# 19_-DDR4_260_PIN_CON.net
KiCad netlist of a schematic drawn in Altium Designer
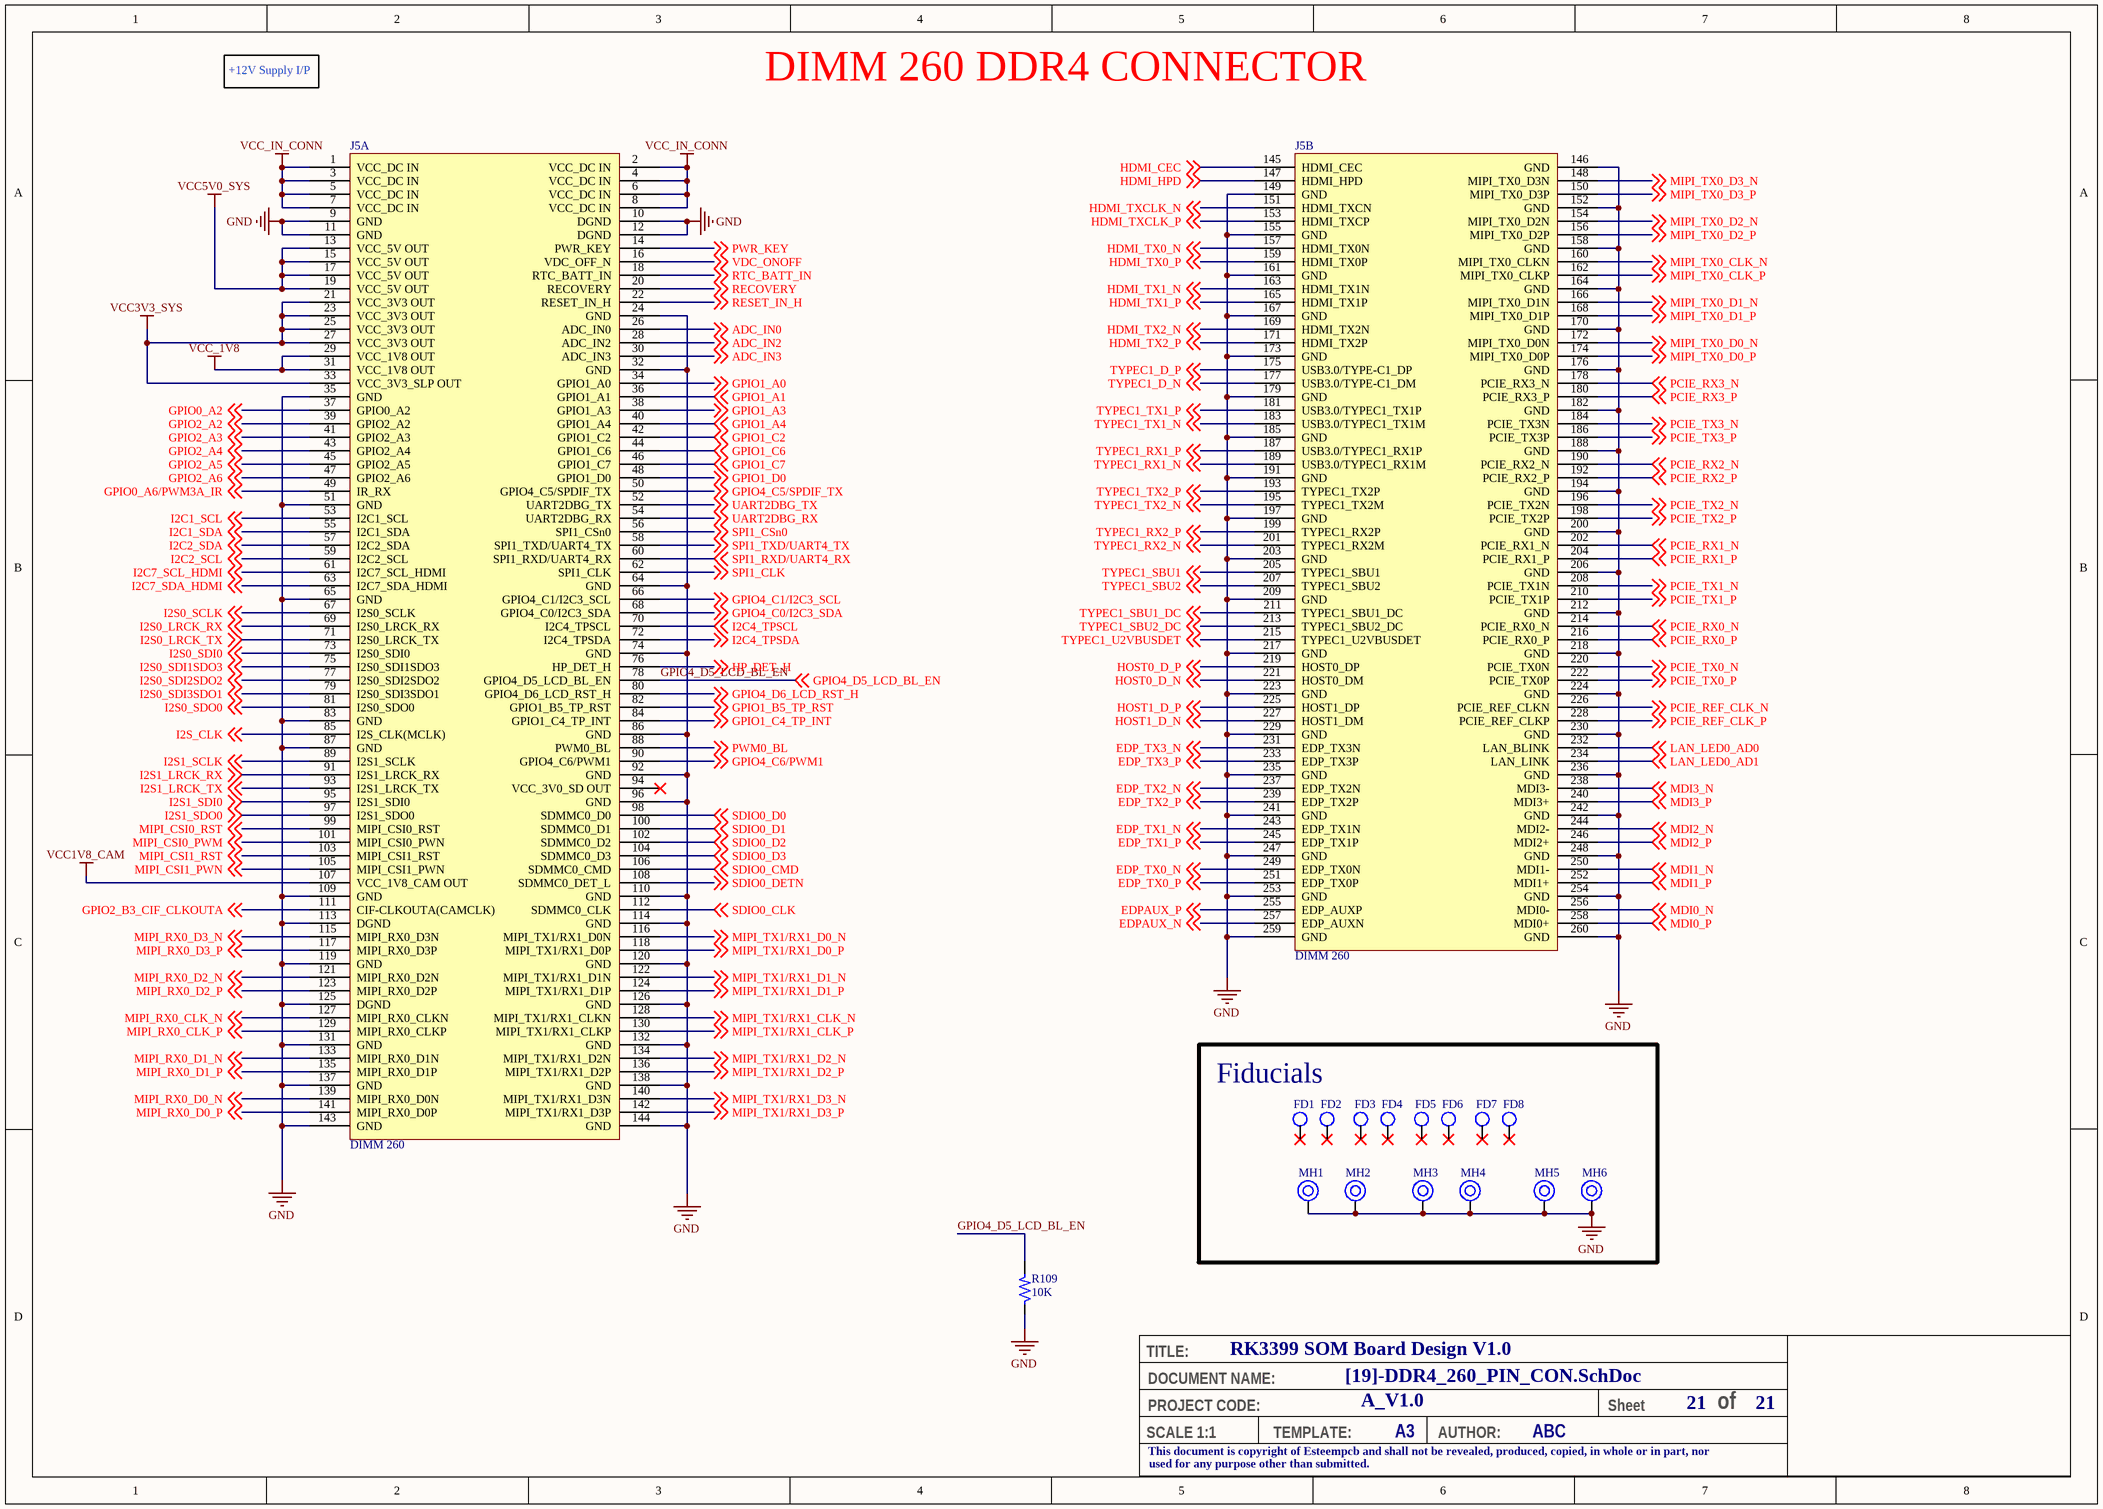
[diagram p0: [19]-DDR4_260_PIN_CON.SchDoc]

(export (version "E")
  (design (tool "Eeschema 10.0.6"))
  (components
    (comp (ref "FD1")
      (value "Fiducial")
      (footprint "FIDUCIAL_50MIL")
      (description "78.7 or 50 mil Fiducials SMD")
      (fields (field (name "MANUFACTURER") "NA"))
      (libsource (lib "EsteemPCB_SOM_Course_intlib") (part "Fiducials"))
    )
    (comp (ref "FD2")
      (value "Fiducial")
      (footprint "FIDUCIAL_50MIL")
      (description "78.7 or 50 mil Fiducials SMD")
      (fields (field (name "MANUFACTURER") "NA"))
      (libsource (lib "EsteemPCB_SOM_Course_intlib") (part "Fiducials"))
    )
    (comp (ref "FD3")
      (value "Fiducial")
      (footprint "FIDUCIAL_50MIL")
      (description "78.7 or 50 mil Fiducials SMD")
      (fields (field (name "MANUFACTURER") "NA"))
      (libsource (lib "EsteemPCB_SOM_Course_intlib") (part "Fiducials"))
    )
    (comp (ref "FD4")
      (value "Fiducial")
      (footprint "FIDUCIAL_50MIL")
      (description "78.7 or 50 mil Fiducials SMD")
      (fields (field (name "MANUFACTURER") "NA"))
      (libsource (lib "EsteemPCB_SOM_Course_intlib") (part "Fiducials"))
    )
    (comp (ref "FD5")
      (value "Fiducial")
      (footprint "FIDUCIAL_50MIL")
      (description "78.7 or 50 mil Fiducials SMD")
      (fields (field (name "MANUFACTURER") "NA"))
      (libsource (lib "EsteemPCB_SOM_Course_intlib") (part "Fiducials"))
    )
    (comp (ref "FD6")
      (value "Fiducial")
      (footprint "FIDUCIAL_50MIL")
      (description "78.7 or 50 mil Fiducials SMD")
      (fields (field (name "MANUFACTURER") "NA"))
      (libsource (lib "EsteemPCB_SOM_Course_intlib") (part "Fiducials"))
    )
    (comp (ref "FD7")
      (value "Fiducial")
      (footprint "FIDUCIAL_50MIL")
      (description "78.7 or 50 mil Fiducials SMD")
      (fields (field (name "MANUFACTURER") "NA"))
      (libsource (lib "EsteemPCB_SOM_Course_intlib") (part "Fiducials"))
    )
    (comp (ref "FD8")
      (value "Fiducial")
      (footprint "FIDUCIAL_50MIL")
      (description "78.7 or 50 mil Fiducials SMD")
      (fields (field (name "MANUFACTURER") "NA"))
      (libsource (lib "EsteemPCB_SOM_Course_intlib") (part "Fiducials"))
    )
    (comp (ref "J5")
      (value "DIMM 260")
      (footprint "DIMM260_DDR4")
      (description "Dimm 260 pin smd plating on pcb")
      (fields (field (name "MANUFACTURER") "NA"))
      (libsource (lib "RK3399 _Module_Schlib") (part "CON-DIMM_260-SMD"))
    )
    (comp (ref "MH1")
      (value "Mounting Hole")
      (footprint "SOM_Mounting")
      (fields (field (name "MANUFACTURER PART NUMBER") "NA"))
      (libsource (lib "EsteemPCB_SOM_Course_intlib") (part "MH_3.5H_6D"))
    )
    (comp (ref "MH2")
      (value "Mounting Hole")
      (footprint "SOM_Mounting")
      (fields (field (name "MANUFACTURER PART NUMBER") "NA"))
      (libsource (lib "EsteemPCB_SOM_Course_intlib") (part "MH_3.5H_6D"))
    )
    (comp (ref "MH3")
      (value "Mounting Hole")
      (footprint "SOM_Mounting")
      (fields (field (name "MANUFACTURER PART NUMBER") "NA"))
      (libsource (lib "EsteemPCB_SOM_Course_intlib") (part "MH_3.5H_6D"))
    )
    (comp (ref "MH4")
      (value "Mounting Hole")
      (footprint "SOM_Mounting")
      (fields (field (name "MANUFACTURER PART NUMBER") "NA"))
      (libsource (lib "EsteemPCB_SOM_Course_intlib") (part "MH_3.5H_6D"))
    )
    (comp (ref "MH5")
      (value "Mounting Hole")
      (footprint "SOM_Mounting")
      (fields (field (name "MANUFACTURER PART NUMBER") "NA"))
      (libsource (lib "EsteemPCB_SOM_Course_intlib") (part "MH_3.5H_6D"))
    )
    (comp (ref "MH6")
      (value "Mounting Hole")
      (footprint "SOM_Mounting")
      (fields (field (name "MANUFACTURER PART NUMBER") "NA"))
      (libsource (lib "EsteemPCB_SOM_Course_intlib") (part "MH_3.5H_6D"))
    )
    (comp (ref "R109")
      (value "10K")
      (footprint "RES_0402")
      (description "10 kOhms ±1% 0.1W, 1/10W Chip Resistor 0402 (1005 Metric) Anti-Sulfur Thin Film")
      (fields
        (field (name "MANUFACTURER") "Vishay Beyschlag/Draloric/BC Components")
        (field (name "MANUFACTURER PART NUMBER") "MCS04020C1002FE000")
      )
      (libsource (lib "RK3399 _Module_Schlib") (part "RES_10K-0.1W-1%-0402"))
    )
  )
  (nets
    (net (code "1") (name "ADC_IN0") (class "Default")
      (node (ref "J5") (pin "26") (pinfunction "ADC_IN0_26") (pintype "passive"))
    )
    (net (code "2") (name "ADC_IN2") (class "Default")
      (node (ref "J5") (pin "28") (pinfunction "ADC_IN2_28") (pintype "passive"))
    )
    (net (code "3") (name "ADC_IN3") (class "Default")
      (node (ref "J5") (pin "30") (pinfunction "ADC_IN3_30") (pintype "passive"))
    )
    (net (code "4") (name "EDPAUX_N") (class "Default")
      (node (ref "J5") (pin "257") (pinfunction "EDP_AUXN_257") (pintype "passive"))
    )
    (net (code "5") (name "EDPAUX_P") (class "Default")
      (node (ref "J5") (pin "255") (pinfunction "EDP_AUXP_255") (pintype "passive"))
    )
    (net (code "6") (name "EDP_TX0_N") (class "Default")
      (node (ref "J5") (pin "249") (pinfunction "EDP_TX0N_249") (pintype "passive"))
    )
    (net (code "7") (name "EDP_TX0_P") (class "Default")
      (node (ref "J5") (pin "251") (pinfunction "EDP_TX0P_251") (pintype "passive"))
    )
    (net (code "8") (name "EDP_TX1_N") (class "Default")
      (node (ref "J5") (pin "243") (pinfunction "EDP_TX1N_243") (pintype "passive"))
    )
    (net (code "9") (name "EDP_TX1_P") (class "Default")
      (node (ref "J5") (pin "245") (pinfunction "EDP_TX1P_245") (pintype "passive"))
    )
    (net (code "10") (name "EDP_TX2_N") (class "Default")
      (node (ref "J5") (pin "237") (pinfunction "EDP_TX2N_237") (pintype "passive"))
    )
    (net (code "11") (name "EDP_TX2_P") (class "Default")
      (node (ref "J5") (pin "239") (pinfunction "EDP_TX2P_239") (pintype "passive"))
    )
    (net (code "12") (name "EDP_TX3_N") (class "Default")
      (node (ref "J5") (pin "231") (pinfunction "EDP_TX3N_231") (pintype "passive"))
    )
    (net (code "13") (name "EDP_TX3_P") (class "Default")
      (node (ref "J5") (pin "233") (pinfunction "EDP_TX3P_233") (pintype "passive"))
    )
    (net (code "14") (name "GND") (class "Default")
      (node (ref "J5") (pin "10") (pinfunction "DGND_10") (pintype "passive"))
      (node (ref "J5") (pin "109") (pinfunction "GND_109") (pintype "passive"))
      (node (ref "J5") (pin "11") (pinfunction "GND_11") (pintype "passive"))
      (node (ref "J5") (pin "110") (pinfunction "GND_110") (pintype "passive"))
      (node (ref "J5") (pin "113") (pinfunction "DGND_113") (pintype "passive"))
      (node (ref "J5") (pin "114") (pinfunction "GND_114") (pintype "passive"))
      (node (ref "J5") (pin "119") (pinfunction "GND_119") (pintype "passive"))
      (node (ref "J5") (pin "12") (pinfunction "DGND_12") (pintype "passive"))
      (node (ref "J5") (pin "120") (pinfunction "GND_120") (pintype "passive"))
      (node (ref "J5") (pin "125") (pinfunction "DGND_125") (pintype "passive"))
      (node (ref "J5") (pin "126") (pinfunction "GND_126") (pintype "passive"))
      (node (ref "J5") (pin "131") (pinfunction "GND_131") (pintype "passive"))
      (node (ref "J5") (pin "132") (pinfunction "GND_132") (pintype "passive"))
      (node (ref "J5") (pin "137") (pinfunction "GND_137") (pintype "passive"))
      (node (ref "J5") (pin "138") (pinfunction "GND_138") (pintype "passive"))
      (node (ref "J5") (pin "143") (pinfunction "GND_143") (pintype "passive"))
      (node (ref "J5") (pin "144") (pinfunction "GND_144") (pintype "passive"))
      (node (ref "J5") (pin "146") (pinfunction "GND_146") (pintype "passive"))
      (node (ref "J5") (pin "149") (pinfunction "GND_149") (pintype "passive"))
      (node (ref "J5") (pin "152") (pinfunction "GND_152") (pintype "passive"))
      (node (ref "J5") (pin "155") (pinfunction "GND_155") (pintype "passive"))
      (node (ref "J5") (pin "158") (pinfunction "GND_158") (pintype "passive"))
      (node (ref "J5") (pin "161") (pinfunction "GND_161") (pintype "passive"))
      (node (ref "J5") (pin "164") (pinfunction "GND_164") (pintype "passive"))
      (node (ref "J5") (pin "167") (pinfunction "GND_167") (pintype "passive"))
      (node (ref "J5") (pin "170") (pinfunction "GND_170") (pintype "passive"))
      (node (ref "J5") (pin "173") (pinfunction "GND_173") (pintype "passive"))
      (node (ref "J5") (pin "176") (pinfunction "GND_176") (pintype "passive"))
      (node (ref "J5") (pin "179") (pinfunction "GND_179") (pintype "passive"))
      (node (ref "J5") (pin "182") (pinfunction "GND_182") (pintype "passive"))
      (node (ref "J5") (pin "185") (pinfunction "GND_185") (pintype "passive"))
      (node (ref "J5") (pin "188") (pinfunction "GND_188") (pintype "passive"))
      (node (ref "J5") (pin "191") (pinfunction "GND_191") (pintype "passive"))
      (node (ref "J5") (pin "194") (pinfunction "GND_194") (pintype "passive"))
      (node (ref "J5") (pin "197") (pinfunction "GND_197") (pintype "passive"))
      (node (ref "J5") (pin "200") (pinfunction "GND_200") (pintype "passive"))
      (node (ref "J5") (pin "203") (pinfunction "GND_203") (pintype "passive"))
      (node (ref "J5") (pin "206") (pinfunction "GND_206") (pintype "passive"))
      (node (ref "J5") (pin "209") (pinfunction "GND_209") (pintype "passive"))
      (node (ref "J5") (pin "212") (pinfunction "GND_212") (pintype "passive"))
      (node (ref "J5") (pin "217") (pinfunction "GND_217") (pintype "passive"))
      (node (ref "J5") (pin "218") (pinfunction "GND_218") (pintype "passive"))
      (node (ref "J5") (pin "223") (pinfunction "GND_223") (pintype "passive"))
      (node (ref "J5") (pin "224") (pinfunction "GND_224") (pintype "passive"))
      (node (ref "J5") (pin "229") (pinfunction "GND_229") (pintype "passive"))
      (node (ref "J5") (pin "230") (pinfunction "GND_230") (pintype "passive"))
      (node (ref "J5") (pin "235") (pinfunction "GND_235") (pintype "passive"))
      (node (ref "J5") (pin "236") (pinfunction "GND_236") (pintype "passive"))
      (node (ref "J5") (pin "24") (pinfunction "GND_24") (pintype "passive"))
      (node (ref "J5") (pin "241") (pinfunction "GND_241") (pintype "passive"))
      (node (ref "J5") (pin "242") (pinfunction "GND_242") (pintype "passive"))
      (node (ref "J5") (pin "247") (pinfunction "GND_247") (pintype "passive"))
      (node (ref "J5") (pin "248") (pinfunction "GND_248") (pintype "passive"))
      (node (ref "J5") (pin "253") (pinfunction "GND_253") (pintype "passive"))
      (node (ref "J5") (pin "254") (pinfunction "GND_254") (pintype "passive"))
      (node (ref "J5") (pin "259") (pinfunction "GND_259") (pintype "passive"))
      (node (ref "J5") (pin "260") (pinfunction "GND_260") (pintype "passive"))
      (node (ref "J5") (pin "32") (pinfunction "GND_32") (pintype "passive"))
      (node (ref "J5") (pin "35") (pinfunction "GND_35") (pintype "passive"))
      (node (ref "J5") (pin "51") (pinfunction "GND_51") (pintype "passive"))
      (node (ref "J5") (pin "64") (pinfunction "GND_64") (pintype "passive"))
      (node (ref "J5") (pin "65") (pinfunction "GND_65") (pintype "passive"))
      (node (ref "J5") (pin "74") (pinfunction "GND_74") (pintype "passive"))
      (node (ref "J5") (pin "83") (pinfunction "GND_83") (pintype "passive"))
      (node (ref "J5") (pin "86") (pinfunction "GND_86") (pintype "passive"))
      (node (ref "J5") (pin "87") (pinfunction "GND_87") (pintype "passive"))
      (node (ref "J5") (pin "9") (pinfunction "GND_9") (pintype "passive"))
      (node (ref "J5") (pin "92") (pinfunction "GND_92") (pintype "passive"))
      (node (ref "J5") (pin "96") (pinfunction "GND_96") (pintype "passive"))
      (node (ref "MH1") (pin "1") (pinfunction "1_1") (pintype "passive"))
      (node (ref "MH2") (pin "1") (pinfunction "1_1") (pintype "passive"))
      (node (ref "MH3") (pin "1") (pinfunction "1_1") (pintype "passive"))
      (node (ref "MH4") (pin "1") (pinfunction "1_1") (pintype "passive"))
      (node (ref "MH5") (pin "1") (pinfunction "1_1") (pintype "passive"))
      (node (ref "MH6") (pin "1") (pinfunction "1_1") (pintype "passive"))
      (node (ref "R109") (pin "1") (pinfunction "1_1") (pintype "passive"))
    )
    (net (code "15") (name "GPIO0_A2") (class "Default")
      (node (ref "J5") (pin "37") (pinfunction "GPIO0_A2_37") (pintype "passive"))
    )
    (net (code "16") (name "GPIO0_A6{slash}PWM3A_IR") (class "Default")
      (node (ref "J5") (pin "49") (pinfunction "IR_RX_49") (pintype "passive"))
    )
    (net (code "17") (name "GPIO1_A0") (class "Default")
      (node (ref "J5") (pin "34") (pinfunction "GPIO1_A0_34") (pintype "passive"))
    )
    (net (code "18") (name "GPIO1_A1") (class "Default")
      (node (ref "J5") (pin "36") (pinfunction "GPIO1_A1_36") (pintype "passive"))
    )
    (net (code "19") (name "GPIO1_A3") (class "Default")
      (node (ref "J5") (pin "38") (pinfunction "GPIO1_A3_38") (pintype "passive"))
    )
    (net (code "20") (name "GPIO1_A4") (class "Default")
      (node (ref "J5") (pin "40") (pinfunction "GPIO1_A4_40") (pintype "passive"))
    )
    (net (code "21") (name "GPIO1_B5_TP_RST") (class "Default")
      (node (ref "J5") (pin "82") (pinfunction "GPIO1_B5_TP_RST_82") (pintype "passive"))
    )
    (net (code "22") (name "GPIO1_C2") (class "Default")
      (node (ref "J5") (pin "42") (pinfunction "GPIO1_C2_42") (pintype "passive"))
    )
    (net (code "23") (name "GPIO1_C4_TP_INT") (class "Default")
      (node (ref "J5") (pin "84") (pinfunction "GPIO1_C4_TP_INT_84") (pintype "passive"))
    )
    (net (code "24") (name "GPIO1_C6") (class "Default")
      (node (ref "J5") (pin "44") (pinfunction "GPIO1_C6_44") (pintype "passive"))
    )
    (net (code "25") (name "GPIO1_C7") (class "Default")
      (node (ref "J5") (pin "46") (pinfunction "GPIO1_C7_46") (pintype "passive"))
    )
    (net (code "26") (name "GPIO1_D0") (class "Default")
      (node (ref "J5") (pin "48") (pinfunction "GPIO1_D0_48") (pintype "passive"))
    )
    (net (code "27") (name "GPIO2_A2") (class "Default")
      (node (ref "J5") (pin "39") (pinfunction "GPIO2_A2_39") (pintype "passive"))
    )
    (net (code "28") (name "GPIO2_A3") (class "Default")
      (node (ref "J5") (pin "41") (pinfunction "GPIO2_A3_41") (pintype "passive"))
    )
    (net (code "29") (name "GPIO2_A4") (class "Default")
      (node (ref "J5") (pin "43") (pinfunction "GPIO2_A4_43") (pintype "passive"))
    )
    (net (code "30") (name "GPIO2_A5") (class "Default")
      (node (ref "J5") (pin "45") (pinfunction "GPIO2_A5_45") (pintype "passive"))
    )
    (net (code "31") (name "GPIO2_A6") (class "Default")
      (node (ref "J5") (pin "47") (pinfunction "GPIO2_A6_47") (pintype "passive"))
    )
    (net (code "32") (name "GPIO2_B3_CIF_CLKOUTA") (class "Default")
      (node (ref "J5") (pin "111") (pinfunction "CIF-CLKOUTA(CAMCLK)_111") (pintype "passive"))
    )
    (net (code "33") (name "GPIO4_C0{slash}I2C3_SDA") (class "Default")
      (node (ref "J5") (pin "68") (pinfunction "GPIO4_C0/I2C3_SDA_68") (pintype "passive"))
    )
    (net (code "34") (name "GPIO4_C1{slash}I2C3_SCL") (class "Default")
      (node (ref "J5") (pin "66") (pinfunction "GPIO4_C1/I2C3_SCL_66") (pintype "passive"))
    )
    (net (code "35") (name "GPIO4_C5{slash}SPDIF_TX") (class "Default")
      (node (ref "J5") (pin "50") (pinfunction "GPIO4_C5/SPDIF_TX_50") (pintype "passive"))
    )
    (net (code "36") (name "GPIO4_C6{slash}PWM1") (class "Default")
      (node (ref "J5") (pin "90") (pinfunction "GPIO4_C6/PWM1_90") (pintype "passive"))
    )
    (net (code "37") (name "GPIO4_D5_LCD_BL_EN") (class "Default")
      (node (ref "J5") (pin "78") (pinfunction "GPIO4_D5_LCD_BL_EN_78") (pintype "passive"))
      (node (ref "R109") (pin "2") (pinfunction "2_2") (pintype "passive"))
    )
    (net (code "38") (name "GPIO4_D6_LCD_RST_H") (class "Default")
      (node (ref "J5") (pin "80") (pinfunction "GPIO4_D6_LCD_RST_H_80") (pintype "passive"))
    )
    (net (code "39") (name "HDMI_CEC") (class "Default")
      (node (ref "J5") (pin "145") (pinfunction "HDMI_CEC_145") (pintype "passive"))
    )
    (net (code "40") (name "HDMI_HPD") (class "Default")
      (node (ref "J5") (pin "147") (pinfunction "HDMI_HPD_147") (pintype "passive"))
    )
    (net (code "41") (name "HDMI_TX0_N") (class "Default")
      (node (ref "J5") (pin "157") (pinfunction "HDMI_TX0N_157") (pintype "passive"))
    )
    (net (code "42") (name "HDMI_TX0_P") (class "Default")
      (node (ref "J5") (pin "159") (pinfunction "HDMI_TX0P_159") (pintype "passive"))
    )
    (net (code "43") (name "HDMI_TX1_N") (class "Default")
      (node (ref "J5") (pin "163") (pinfunction "HDMI_TX1N_163") (pintype "passive"))
    )
    (net (code "44") (name "HDMI_TX1_P") (class "Default")
      (node (ref "J5") (pin "165") (pinfunction "HDMI_TX1P_165") (pintype "passive"))
    )
    (net (code "45") (name "HDMI_TX2_N") (class "Default")
      (node (ref "J5") (pin "169") (pinfunction "HDMI_TX2N_169") (pintype "passive"))
    )
    (net (code "46") (name "HDMI_TX2_P") (class "Default")
      (node (ref "J5") (pin "171") (pinfunction "HDMI_TX2P_171") (pintype "passive"))
    )
    (net (code "47") (name "HDMI_TXCLK_N") (class "Default")
      (node (ref "J5") (pin "151") (pinfunction "HDMI_TXCN_151") (pintype "passive"))
    )
    (net (code "48") (name "HDMI_TXCLK_P") (class "Default")
      (node (ref "J5") (pin "153") (pinfunction "HDMI_TXCP_153") (pintype "passive"))
    )
    (net (code "49") (name "HOST0_D_N") (class "Default")
      (node (ref "J5") (pin "221") (pinfunction "HOST0_DM_221") (pintype "passive"))
    )
    (net (code "50") (name "HOST0_D_P") (class "Default")
      (node (ref "J5") (pin "219") (pinfunction "HOST0_DP_219") (pintype "passive"))
    )
    (net (code "51") (name "HOST1_D_N") (class "Default")
      (node (ref "J5") (pin "227") (pinfunction "HOST1_DM_227") (pintype "passive"))
    )
    (net (code "52") (name "HOST1_D_P") (class "Default")
      (node (ref "J5") (pin "225") (pinfunction "HOST1_DP_225") (pintype "passive"))
    )
    (net (code "53") (name "HP_DET_H") (class "Default")
      (node (ref "J5") (pin "76") (pinfunction "HP_DET_H_76") (pintype "passive"))
    )
    (net (code "54") (name "I2C1_SCL") (class "Default")
      (node (ref "J5") (pin "53") (pinfunction "I2C1_SCL_53") (pintype "passive"))
    )
    (net (code "55") (name "I2C1_SDA") (class "Default")
      (node (ref "J5") (pin "55") (pinfunction "I2C1_SDA_55") (pintype "passive"))
    )
    (net (code "56") (name "I2C2_SCL") (class "Default")
      (node (ref "J5") (pin "59") (pinfunction "I2C2_SCL_59") (pintype "passive"))
    )
    (net (code "57") (name "I2C2_SDA") (class "Default")
      (node (ref "J5") (pin "57") (pinfunction "I2C2_SDA_57") (pintype "passive"))
    )
    (net (code "58") (name "I2C4_TPSCL") (class "Default")
      (node (ref "J5") (pin "70") (pinfunction "I2C4_TPSCL_70") (pintype "passive"))
    )
    (net (code "59") (name "I2C4_TPSDA") (class "Default")
      (node (ref "J5") (pin "72") (pinfunction "I2C4_TPSDA_72") (pintype "passive"))
    )
    (net (code "60") (name "I2C7_SCL_HDMI") (class "Default")
      (node (ref "J5") (pin "61") (pinfunction "I2C7_SCL_HDMI_61") (pintype "passive"))
    )
    (net (code "61") (name "I2C7_SDA_HDMI") (class "Default")
      (node (ref "J5") (pin "63") (pinfunction "I2C7_SDA_HDMI_63") (pintype "passive"))
    )
    (net (code "62") (name "I2S0_LRCK_RX") (class "Default")
      (node (ref "J5") (pin "69") (pinfunction "I2S0_LRCK_RX_69") (pintype "passive"))
    )
    (net (code "63") (name "I2S0_LRCK_TX") (class "Default")
      (node (ref "J5") (pin "71") (pinfunction "I2S0_LRCK_TX_71") (pintype "passive"))
    )
    (net (code "64") (name "I2S0_SCLK") (class "Default")
      (node (ref "J5") (pin "67") (pinfunction "I2S0_SCLK_67") (pintype "passive"))
    )
    (net (code "65") (name "I2S0_SDI0") (class "Default")
      (node (ref "J5") (pin "73") (pinfunction "I2S0_SDI0_73") (pintype "passive"))
    )
    (net (code "66") (name "I2S0_SDI1SDO3") (class "Default")
      (node (ref "J5") (pin "75") (pinfunction "I2S0_SDI1SDO3_75") (pintype "passive"))
    )
    (net (code "67") (name "I2S0_SDI2SDO2") (class "Default")
      (node (ref "J5") (pin "77") (pinfunction "I2S0_SDI2SDO2_77") (pintype "passive"))
    )
    (net (code "68") (name "I2S0_SDI3SDO1") (class "Default")
      (node (ref "J5") (pin "79") (pinfunction "I2S0_SDI3SDO1_79") (pintype "passive"))
    )
    (net (code "69") (name "I2S0_SDO0") (class "Default")
      (node (ref "J5") (pin "81") (pinfunction "I2S0_SDO0_81") (pintype "passive"))
    )
    (net (code "70") (name "I2S1_LRCK_RX") (class "Default")
      (node (ref "J5") (pin "91") (pinfunction "I2S1_LRCK_RX_91") (pintype "passive"))
    )
    (net (code "71") (name "I2S1_LRCK_TX") (class "Default")
      (node (ref "J5") (pin "93") (pinfunction "I2S1_LRCK_TX_93") (pintype "passive"))
    )
    (net (code "72") (name "I2S1_SCLK") (class "Default")
      (node (ref "J5") (pin "89") (pinfunction "I2S1_SCLK_89") (pintype "passive"))
    )
    (net (code "73") (name "I2S1_SDI0") (class "Default")
      (node (ref "J5") (pin "95") (pinfunction "I2S1_SDI0_95") (pintype "passive"))
    )
    (net (code "74") (name "I2S1_SDO0") (class "Default")
      (node (ref "J5") (pin "97") (pinfunction "I2S1_SDO0_97") (pintype "passive"))
    )
    (net (code "75") (name "I2S_CLK") (class "Default")
      (node (ref "J5") (pin "85") (pinfunction "I2S_CLK(MCLK)_85") (pintype "passive"))
    )
    (net (code "76") (name "LAN_LED0_AD0") (class "Default")
      (node (ref "J5") (pin "232") (pinfunction "LAN_BLINK_232") (pintype "passive"))
    )
    (net (code "77") (name "LAN_LED0_AD1") (class "Default")
      (node (ref "J5") (pin "234") (pinfunction "LAN_LINK_234") (pintype "passive"))
    )
    (net (code "78") (name "MDI0_N") (class "Default")
      (node (ref "J5") (pin "256") (pinfunction "MDI0-_256") (pintype "passive"))
    )
    (net (code "79") (name "MDI0_P") (class "Default")
      (node (ref "J5") (pin "258") (pinfunction "MDI0+_258") (pintype "passive"))
    )
    (net (code "80") (name "MDI1_N") (class "Default")
      (node (ref "J5") (pin "250") (pinfunction "MDI1-_250") (pintype "passive"))
    )
    (net (code "81") (name "MDI1_P") (class "Default")
      (node (ref "J5") (pin "252") (pinfunction "MDI1+_252") (pintype "passive"))
    )
    (net (code "82") (name "MDI2_N") (class "Default")
      (node (ref "J5") (pin "244") (pinfunction "MDI2-_244") (pintype "passive"))
    )
    (net (code "83") (name "MDI2_P") (class "Default")
      (node (ref "J5") (pin "246") (pinfunction "MDI2+_246") (pintype "passive"))
    )
    (net (code "84") (name "MDI3_N") (class "Default")
      (node (ref "J5") (pin "238") (pinfunction "MDI3-_238") (pintype "passive"))
    )
    (net (code "85") (name "MDI3_P") (class "Default")
      (node (ref "J5") (pin "240") (pinfunction "MDI3+_240") (pintype "passive"))
    )
    (net (code "86") (name "MIPI_CSI0_PWM") (class "Default")
      (node (ref "J5") (pin "101") (pinfunction "MIPI_CSI0_PWN_101") (pintype "passive"))
    )
    (net (code "87") (name "MIPI_CSI0_RST") (class "Default")
      (node (ref "J5") (pin "99") (pinfunction "MIPI_CSI0_RST_99") (pintype "passive"))
    )
    (net (code "88") (name "MIPI_CSI1_PWN") (class "Default")
      (node (ref "J5") (pin "105") (pinfunction "MIPI_CSI1_PWN_105") (pintype "passive"))
    )
    (net (code "89") (name "MIPI_CSI1_RST") (class "Default")
      (node (ref "J5") (pin "103") (pinfunction "MIPI_CSI1_RST_103") (pintype "passive"))
    )
    (net (code "90") (name "MIPI_RX0_CLK_N") (class "Default")
      (node (ref "J5") (pin "127") (pinfunction "MIPI_RX0_CLKN_127") (pintype "passive"))
    )
    (net (code "91") (name "MIPI_RX0_CLK_P") (class "Default")
      (node (ref "J5") (pin "129") (pinfunction "MIPI_RX0_CLKP_129") (pintype "passive"))
    )
    (net (code "92") (name "MIPI_RX0_D0_N") (class "Default")
      (node (ref "J5") (pin "139") (pinfunction "MIPI_RX0_D0N_139") (pintype "passive"))
    )
    (net (code "93") (name "MIPI_RX0_D0_P") (class "Default")
      (node (ref "J5") (pin "141") (pinfunction "MIPI_RX0_D0P_141") (pintype "passive"))
    )
    (net (code "94") (name "MIPI_RX0_D1_N") (class "Default")
      (node (ref "J5") (pin "133") (pinfunction "MIPI_RX0_D1N_133") (pintype "passive"))
    )
    (net (code "95") (name "MIPI_RX0_D1_P") (class "Default")
      (node (ref "J5") (pin "135") (pinfunction "MIPI_RX0_D1P_135") (pintype "passive"))
    )
    (net (code "96") (name "MIPI_RX0_D2_N") (class "Default")
      (node (ref "J5") (pin "121") (pinfunction "MIPI_RX0_D2N_121") (pintype "passive"))
    )
    (net (code "97") (name "MIPI_RX0_D2_P") (class "Default")
      (node (ref "J5") (pin "123") (pinfunction "MIPI_RX0_D2P_123") (pintype "passive"))
    )
    (net (code "98") (name "MIPI_RX0_D3_N") (class "Default")
      (node (ref "J5") (pin "115") (pinfunction "MIPI_RX0_D3N_115") (pintype "passive"))
    )
    (net (code "99") (name "MIPI_RX0_D3_P") (class "Default")
      (node (ref "J5") (pin "117") (pinfunction "MIPI_RX0_D3P_117") (pintype "passive"))
    )
    (net (code "100") (name "MIPI_TX0_CLK_N") (class "Default")
      (node (ref "J5") (pin "160") (pinfunction "MIPI_TX0_CLKN_160") (pintype "passive"))
    )
    (net (code "101") (name "MIPI_TX0_CLK_P") (class "Default")
      (node (ref "J5") (pin "162") (pinfunction "MIPI_TX0_CLKP_162") (pintype "passive"))
    )
    (net (code "102") (name "MIPI_TX0_D0_N") (class "Default")
      (node (ref "J5") (pin "172") (pinfunction "MIPI_TX0_D0N_172") (pintype "passive"))
    )
    (net (code "103") (name "MIPI_TX0_D0_P") (class "Default")
      (node (ref "J5") (pin "174") (pinfunction "MIPI_TX0_D0P_174") (pintype "passive"))
    )
    (net (code "104") (name "MIPI_TX0_D1_N") (class "Default")
      (node (ref "J5") (pin "166") (pinfunction "MIPI_TX0_D1N_166") (pintype "passive"))
    )
    (net (code "105") (name "MIPI_TX0_D1_P") (class "Default")
      (node (ref "J5") (pin "168") (pinfunction "MIPI_TX0_D1P_168") (pintype "passive"))
    )
    (net (code "106") (name "MIPI_TX0_D2_N") (class "Default")
      (node (ref "J5") (pin "154") (pinfunction "MIPI_TX0_D2N_154") (pintype "passive"))
    )
    (net (code "107") (name "MIPI_TX0_D2_P") (class "Default")
      (node (ref "J5") (pin "156") (pinfunction "MIPI_TX0_D2P_156") (pintype "passive"))
    )
    (net (code "108") (name "MIPI_TX0_D3_N") (class "Default")
      (node (ref "J5") (pin "148") (pinfunction "MIPI_TX0_D3N_148") (pintype "passive"))
    )
    (net (code "109") (name "MIPI_TX0_D3_P") (class "Default")
      (node (ref "J5") (pin "150") (pinfunction "MIPI_TX0_D3P_150") (pintype "passive"))
    )
    (net (code "110") (name "MIPI_TX1{slash}RX1_CLK_N") (class "Default")
      (node (ref "J5") (pin "128") (pinfunction "MIPI_TX1/RX1_CLKN_128") (pintype "passive"))
    )
    (net (code "111") (name "MIPI_TX1{slash}RX1_CLK_P") (class "Default")
      (node (ref "J5") (pin "130") (pinfunction "MIPI_TX1/RX1_CLKP_130") (pintype "passive"))
    )
    (net (code "112") (name "MIPI_TX1{slash}RX1_D0_N") (class "Default")
      (node (ref "J5") (pin "116") (pinfunction "MIPI_TX1/RX1_D0N_116") (pintype "passive"))
    )
    (net (code "113") (name "MIPI_TX1{slash}RX1_D0_P") (class "Default")
      (node (ref "J5") (pin "118") (pinfunction "MIPI_TX1/RX1_D0P_118") (pintype "passive"))
    )
    (net (code "114") (name "MIPI_TX1{slash}RX1_D1_N") (class "Default")
      (node (ref "J5") (pin "122") (pinfunction "MIPI_TX1/RX1_D1N_122") (pintype "passive"))
    )
    (net (code "115") (name "MIPI_TX1{slash}RX1_D1_P") (class "Default")
      (node (ref "J5") (pin "124") (pinfunction "MIPI_TX1/RX1_D1P_124") (pintype "passive"))
    )
    (net (code "116") (name "MIPI_TX1{slash}RX1_D2_N") (class "Default")
      (node (ref "J5") (pin "134") (pinfunction "MIPI_TX1/RX1_D2N_134") (pintype "passive"))
    )
    (net (code "117") (name "MIPI_TX1{slash}RX1_D2_P") (class "Default")
      (node (ref "J5") (pin "136") (pinfunction "MIPI_TX1/RX1_D2P_136") (pintype "passive"))
    )
    (net (code "118") (name "MIPI_TX1{slash}RX1_D3_N") (class "Default")
      (node (ref "J5") (pin "140") (pinfunction "MIPI_TX1/RX1_D3N_140") (pintype "passive"))
    )
    (net (code "119") (name "MIPI_TX1{slash}RX1_D3_P") (class "Default")
      (node (ref "J5") (pin "142") (pinfunction "MIPI_TX1/RX1_D3P_142") (pintype "passive"))
    )
    (net (code "120") (name "PCIE_REF_CLK_N") (class "Default")
      (node (ref "J5") (pin "226") (pinfunction "PCIE_REF_CLKN_226") (pintype "passive"))
    )
    (net (code "121") (name "PCIE_REF_CLK_P") (class "Default")
      (node (ref "J5") (pin "228") (pinfunction "PCIE_REF_CLKP_228") (pintype "passive"))
    )
    (net (code "122") (name "PCIE_RX0_N") (class "Default")
      (node (ref "J5") (pin "214") (pinfunction "PCIE_RX0_N_214") (pintype "passive"))
    )
    (net (code "123") (name "PCIE_RX0_P") (class "Default")
      (node (ref "J5") (pin "216") (pinfunction "PCIE_RX0_P_216") (pintype "passive"))
    )
    (net (code "124") (name "PCIE_RX1_N") (class "Default")
      (node (ref "J5") (pin "202") (pinfunction "PCIE_RX1_N_202") (pintype "passive"))
    )
    (net (code "125") (name "PCIE_RX1_P") (class "Default")
      (node (ref "J5") (pin "204") (pinfunction "PCIE_RX1_P_204") (pintype "passive"))
    )
    (net (code "126") (name "PCIE_RX2_N") (class "Default")
      (node (ref "J5") (pin "190") (pinfunction "PCIE_RX2_N_190") (pintype "passive"))
    )
    (net (code "127") (name "PCIE_RX2_P") (class "Default")
      (node (ref "J5") (pin "192") (pinfunction "PCIE_RX2_P_192") (pintype "passive"))
    )
    (net (code "128") (name "PCIE_RX3_N") (class "Default")
      (node (ref "J5") (pin "178") (pinfunction "PCIE_RX3_N_178") (pintype "passive"))
    )
    (net (code "129") (name "PCIE_RX3_P") (class "Default")
      (node (ref "J5") (pin "180") (pinfunction "PCIE_RX3_P_180") (pintype "passive"))
    )
    (net (code "130") (name "PCIE_TX0_N") (class "Default")
      (node (ref "J5") (pin "220") (pinfunction "PCIE_TX0N_220") (pintype "passive"))
    )
    (net (code "131") (name "PCIE_TX0_P") (class "Default")
      (node (ref "J5") (pin "222") (pinfunction "PCIE_TX0P_222") (pintype "passive"))
    )
    (net (code "132") (name "PCIE_TX1_N") (class "Default")
      (node (ref "J5") (pin "208") (pinfunction "PCIE_TX1N_208") (pintype "passive"))
    )
    (net (code "133") (name "PCIE_TX1_P") (class "Default")
      (node (ref "J5") (pin "210") (pinfunction "PCIE_TX1P_210") (pintype "passive"))
    )
    (net (code "134") (name "PCIE_TX2_N") (class "Default")
      (node (ref "J5") (pin "196") (pinfunction "PCIE_TX2N_196") (pintype "passive"))
    )
    (net (code "135") (name "PCIE_TX2_P") (class "Default")
      (node (ref "J5") (pin "198") (pinfunction "PCIE_TX2P_198") (pintype "passive"))
    )
    (net (code "136") (name "PCIE_TX3_N") (class "Default")
      (node (ref "J5") (pin "184") (pinfunction "PCIE_TX3N_184") (pintype "passive"))
    )
    (net (code "137") (name "PCIE_TX3_P") (class "Default")
      (node (ref "J5") (pin "186") (pinfunction "PCIE_TX3P_186") (pintype "passive"))
    )
    (net (code "138") (name "PWM0_BL") (class "Default")
      (node (ref "J5") (pin "88") (pinfunction "PWM0_BL_88") (pintype "passive"))
    )
    (net (code "139") (name "PWR_KEY") (class "Default")
      (node (ref "J5") (pin "14") (pinfunction "PWR_KEY_14") (pintype "passive"))
    )
    (net (code "140") (name "RECOVERY") (class "Default")
      (node (ref "J5") (pin "20") (pinfunction "RECOVERY_20") (pintype "passive"))
    )
    (net (code "141") (name "RESET_IN_H") (class "Default")
      (node (ref "J5") (pin "22") (pinfunction "RESET_IN_H_22") (pintype "passive"))
    )
    (net (code "142") (name "RTC_BATT_IN") (class "Default")
      (node (ref "J5") (pin "18") (pinfunction "RTC_BATT_IN_18") (pintype "passive"))
    )
    (net (code "143") (name "SDIO0_CLK") (class "Default")
      (node (ref "J5") (pin "112") (pinfunction "SDMMC0_CLK_112") (pintype "passive"))
    )
    (net (code "144") (name "SDIO0_CMD") (class "Default")
      (node (ref "J5") (pin "106") (pinfunction "SDMMC0_CMD_106") (pintype "passive"))
    )
    (net (code "145") (name "SDIO0_D0") (class "Default")
      (node (ref "J5") (pin "98") (pinfunction "SDMMC0_D0_98") (pintype "passive"))
    )
    (net (code "146") (name "SDIO0_D1") (class "Default")
      (node (ref "J5") (pin "100") (pinfunction "SDMMC0_D1_100") (pintype "passive"))
    )
    (net (code "147") (name "SDIO0_D2") (class "Default")
      (node (ref "J5") (pin "102") (pinfunction "SDMMC0_D2_102") (pintype "passive"))
    )
    (net (code "148") (name "SDIO0_D3") (class "Default")
      (node (ref "J5") (pin "104") (pinfunction "SDMMC0_D3_104") (pintype "passive"))
    )
    (net (code "149") (name "SDIO0_DETN") (class "Default")
      (node (ref "J5") (pin "108") (pinfunction "SDMMC0_DET_L_108") (pintype "passive"))
    )
    (net (code "150") (name "SPI1_CLK") (class "Default")
      (node (ref "J5") (pin "62") (pinfunction "SPI1_CLK_62") (pintype "passive"))
    )
    (net (code "151") (name "SPI1_CSn0") (class "Default")
      (node (ref "J5") (pin "56") (pinfunction "SPI1_CSn0_56") (pintype "passive"))
    )
    (net (code "152") (name "SPI1_RXD{slash}UART4_RX") (class "Default")
      (node (ref "J5") (pin "60") (pinfunction "SPI1_RXD/UART4_RX_60") (pintype "passive"))
    )
    (net (code "153") (name "SPI1_TXD{slash}UART4_TX") (class "Default")
      (node (ref "J5") (pin "58") (pinfunction "SPI1_TXD/UART4_TX_58") (pintype "passive"))
    )
    (net (code "154") (name "TYPEC1_D_N") (class "Default")
      (node (ref "J5") (pin "177") (pinfunction "USB3.0/TYPE-C1_DM_177") (pintype "passive"))
    )
    (net (code "155") (name "TYPEC1_D_P") (class "Default")
      (node (ref "J5") (pin "175") (pinfunction "USB3.0/TYPE-C1_DP_175") (pintype "passive"))
    )
    (net (code "156") (name "TYPEC1_RX1_N") (class "Default")
      (node (ref "J5") (pin "189") (pinfunction "USB3.0/TYPEC1_RX1M_189") (pintype "passive"))
    )
    (net (code "157") (name "TYPEC1_RX1_P") (class "Default")
      (node (ref "J5") (pin "187") (pinfunction "USB3.0/TYPEC1_RX1P_187") (pintype "passive"))
    )
    (net (code "158") (name "TYPEC1_RX2_N") (class "Default")
      (node (ref "J5") (pin "201") (pinfunction "TYPEC1_RX2M_201") (pintype "passive"))
    )
    (net (code "159") (name "TYPEC1_RX2_P") (class "Default")
      (node (ref "J5") (pin "199") (pinfunction "TYPEC1_RX2P_199") (pintype "passive"))
    )
    (net (code "160") (name "TYPEC1_SBU1") (class "Default")
      (node (ref "J5") (pin "205") (pinfunction "TYPEC1_SBU1_205") (pintype "passive"))
    )
    (net (code "161") (name "TYPEC1_SBU1_DC") (class "Default")
      (node (ref "J5") (pin "211") (pinfunction "TYPEC1_SBU1_DC_211") (pintype "passive"))
    )
    (net (code "162") (name "TYPEC1_SBU2") (class "Default")
      (node (ref "J5") (pin "207") (pinfunction "TYPEC1_SBU2_207") (pintype "passive"))
    )
    (net (code "163") (name "TYPEC1_SBU2_DC") (class "Default")
      (node (ref "J5") (pin "213") (pinfunction "TYPEC1_SBU2_DC_213") (pintype "passive"))
    )
    (net (code "164") (name "TYPEC1_TX1_N") (class "Default")
      (node (ref "J5") (pin "183") (pinfunction "USB3.0/TYPEC1_TX1M_183") (pintype "passive"))
    )
    (net (code "165") (name "TYPEC1_TX1_P") (class "Default")
      (node (ref "J5") (pin "181") (pinfunction "USB3.0/TYPEC1_TX1P_181") (pintype "passive"))
    )
    (net (code "166") (name "TYPEC1_TX2_N") (class "Default")
      (node (ref "J5") (pin "195") (pinfunction "TYPEC1_TX2M_195") (pintype "passive"))
    )
    (net (code "167") (name "TYPEC1_TX2_P") (class "Default")
      (node (ref "J5") (pin "193") (pinfunction "TYPEC1_TX2P_193") (pintype "passive"))
    )
    (net (code "168") (name "TYPEC1_U2VBUSDET") (class "Default")
      (node (ref "J5") (pin "215") (pinfunction "TYPEC1_U2VBUSDET_215") (pintype "passive"))
    )
    (net (code "169") (name "UART2DBG_RX") (class "Default")
      (node (ref "J5") (pin "54") (pinfunction "UART2DBG_RX_54") (pintype "passive"))
    )
    (net (code "170") (name "UART2DBG_TX") (class "Default")
      (node (ref "J5") (pin "52") (pinfunction "UART2DBG_TX_52") (pintype "passive"))
    )
    (net (code "171") (name "VCC1V8_CAM") (class "Default")
      (node (ref "J5") (pin "107") (pinfunction "VCC_1V8_CAM_OUT_107") (pintype "passive"))
    )
    (net (code "172") (name "VCC3V3_SYS") (class "Default")
      (node (ref "J5") (pin "21") (pinfunction "VCC_3V3_OUT_21") (pintype "passive"))
      (node (ref "J5") (pin "23") (pinfunction "VCC_3V3_OUT_23") (pintype "passive"))
      (node (ref "J5") (pin "25") (pinfunction "VCC_3V3_OUT_25") (pintype "passive"))
      (node (ref "J5") (pin "27") (pinfunction "VCC_3V3_OUT_27") (pintype "passive"))
      (node (ref "J5") (pin "33") (pinfunction "VCC_3V3_SLP_OUT_33") (pintype "passive"))
    )
    (net (code "173") (name "VCC5V0_SYS") (class "Default")
      (node (ref "J5") (pin "13") (pinfunction "VCC_5V_OUT_13") (pintype "passive"))
      (node (ref "J5") (pin "15") (pinfunction "VCC_5V_OUT_15") (pintype "passive"))
      (node (ref "J5") (pin "17") (pinfunction "VCC_5V_OUT_17") (pintype "passive"))
      (node (ref "J5") (pin "19") (pinfunction "VCC_5V_OUT_19") (pintype "passive"))
    )
    (net (code "174") (name "VCC_1V8") (class "Default")
      (node (ref "J5") (pin "29") (pinfunction "VCC_1V8_OUT_29") (pintype "passive"))
      (node (ref "J5") (pin "31") (pinfunction "VCC_1V8_OUT_31") (pintype "passive"))
    )
    (net (code "175") (name "VCC_IN_CONN") (class "Default")
      (node (ref "J5") (pin "1") (pinfunction "VCC_DC_IN_1") (pintype "passive"))
      (node (ref "J5") (pin "2") (pinfunction "VCC_DC_IN_2") (pintype "passive"))
      (node (ref "J5") (pin "3") (pinfunction "VCC_DC_IN_3") (pintype "passive"))
      (node (ref "J5") (pin "4") (pinfunction "VCC_DC_IN_4") (pintype "passive"))
      (node (ref "J5") (pin "5") (pinfunction "VCC_DC_IN_5") (pintype "passive"))
      (node (ref "J5") (pin "6") (pinfunction "VCC_DC_IN_6") (pintype "passive"))
      (node (ref "J5") (pin "7") (pinfunction "VCC_DC_IN_7") (pintype "passive"))
      (node (ref "J5") (pin "8") (pinfunction "VCC_DC_IN_8") (pintype "passive"))
    )
    (net (code "176") (name "VDC_ONOFF") (class "Default")
      (node (ref "J5") (pin "16") (pinfunction "VDC_OFF_N_16") (pintype "passive"))
    )
    (net (code "177") (name "unconnected-(FD1-Pad1)") (class "Default")
      (node (ref "FD1") (pin "1") (pinfunction "1_1") (pintype "passive+no_connect"))
    )
    (net (code "178") (name "unconnected-(FD2-Pad1)") (class "Default")
      (node (ref "FD2") (pin "1") (pinfunction "1_1") (pintype "passive+no_connect"))
    )
    (net (code "179") (name "unconnected-(FD3-Pad1)") (class "Default")
      (node (ref "FD3") (pin "1") (pinfunction "1_1") (pintype "passive+no_connect"))
    )
    (net (code "180") (name "unconnected-(FD4-Pad1)") (class "Default")
      (node (ref "FD4") (pin "1") (pinfunction "1_1") (pintype "passive+no_connect"))
    )
    (net (code "181") (name "unconnected-(FD5-Pad1)") (class "Default")
      (node (ref "FD5") (pin "1") (pinfunction "1_1") (pintype "passive+no_connect"))
    )
    (net (code "182") (name "unconnected-(FD6-Pad1)") (class "Default")
      (node (ref "FD6") (pin "1") (pinfunction "1_1") (pintype "passive+no_connect"))
    )
    (net (code "183") (name "unconnected-(FD7-Pad1)") (class "Default")
      (node (ref "FD7") (pin "1") (pinfunction "1_1") (pintype "passive+no_connect"))
    )
    (net (code "184") (name "unconnected-(FD8-Pad1)") (class "Default")
      (node (ref "FD8") (pin "1") (pinfunction "1_1") (pintype "passive+no_connect"))
    )
    (net (code "185") (name "unconnected-(J5A-VCC_3V0_SD_OUT-Pad94)") (class "Default")
      (node (ref "J5") (pin "94") (pinfunction "VCC_3V0_SD_OUT_94") (pintype "passive+no_connect"))
    )
  )
)
